# Regulator_Schematic.net
KiCad netlist of a schematic drawn in EAGLE
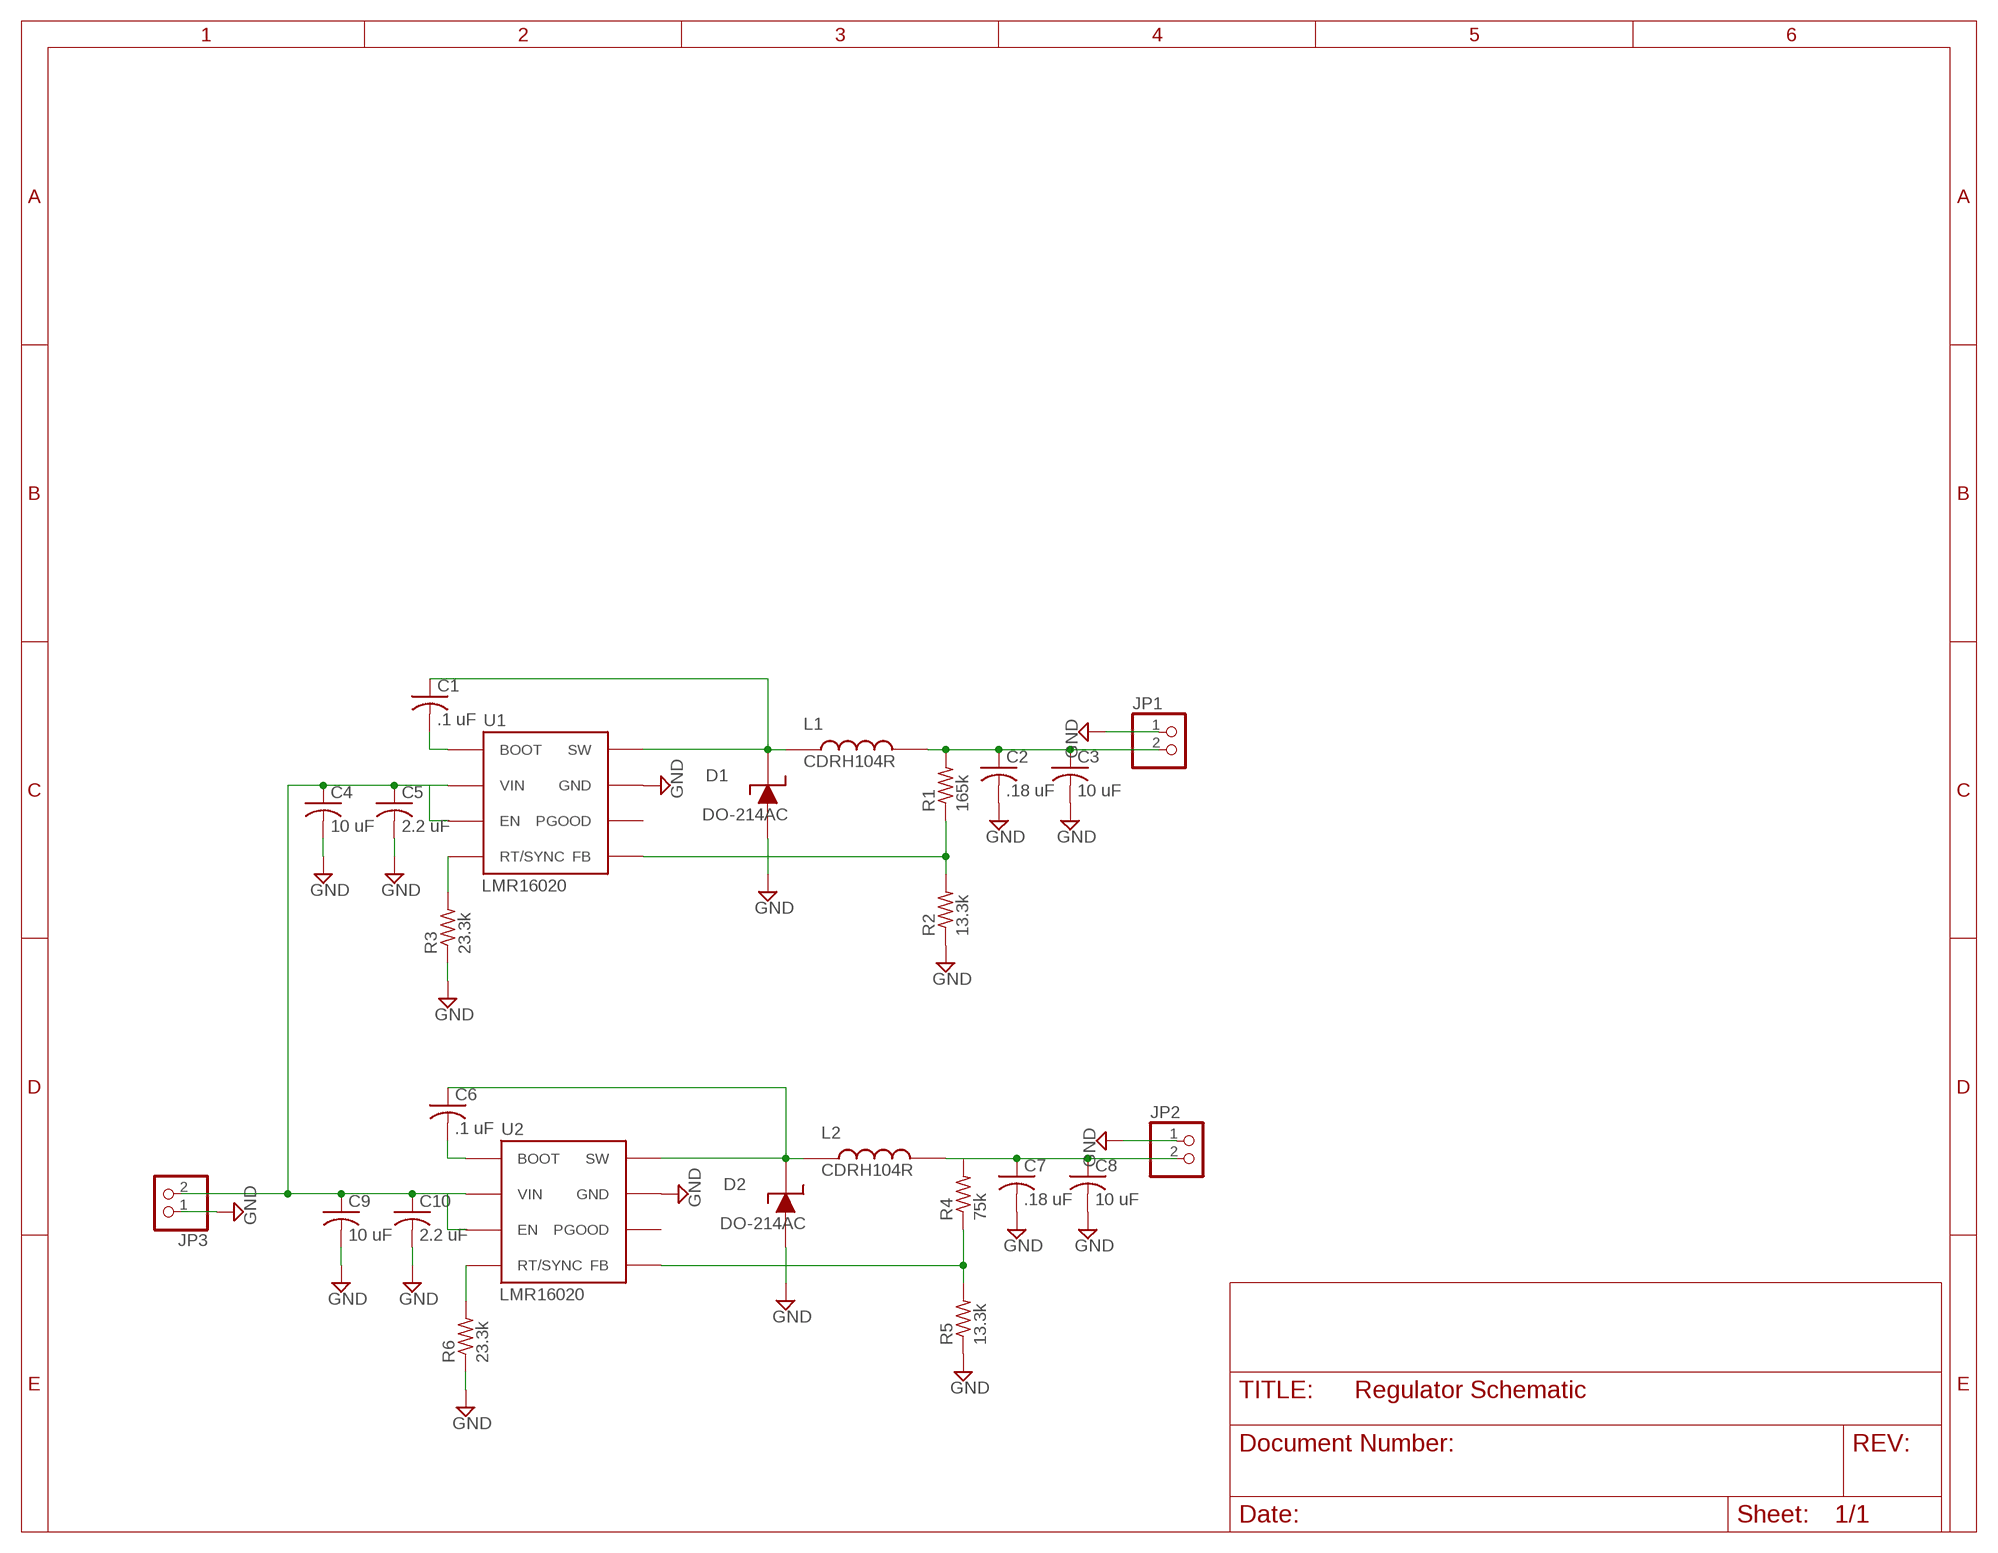
[diagram p0: schematic, sheet 1]

(export (version "E")
  (design (tool "Eeschema 10.0.6"))
  (components
    (comp (ref "C1")
      (value ".1 uF")
      (footprint "eagle-import:C0603")
      (libsource (lib "eagle-import") (part "C-USC0603"))
    )
    (comp (ref "C2")
      (value ".18 uF")
      (footprint "eagle-import:C0603")
      (libsource (lib "eagle-import") (part "C-USC0603"))
    )
    (comp (ref "C3")
      (value "10 uF")
      (footprint "eagle-import:C0603")
      (libsource (lib "eagle-import") (part "C-USC0603"))
    )
    (comp (ref "C4")
      (value "10 uF")
      (footprint "eagle-import:C1210")
      (libsource (lib "eagle-import") (part "C-USC1210"))
    )
    (comp (ref "C5")
      (value "2.2 uF")
      (footprint "eagle-import:C1210")
      (libsource (lib "eagle-import") (part "C-USC1210"))
    )
    (comp (ref "C6")
      (value ".1 uF")
      (footprint "eagle-import:C0603")
      (libsource (lib "eagle-import") (part "C-USC0603"))
    )
    (comp (ref "C7")
      (value ".18 uF")
      (footprint "eagle-import:C0603")
      (libsource (lib "eagle-import") (part "C-USC0603"))
    )
    (comp (ref "C8")
      (value "10 uF")
      (footprint "eagle-import:C0603")
      (libsource (lib "eagle-import") (part "C-USC0603"))
    )
    (comp (ref "C9")
      (value "10 uF")
      (footprint "eagle-import:C1210")
      (libsource (lib "eagle-import") (part "C-USC1210"))
    )
    (comp (ref "C10")
      (value "2.2 uF")
      (footprint "eagle-import:C1210")
      (libsource (lib "eagle-import") (part "C-USC1210"))
    )
    (comp (ref "D1")
      (value "DO-214AC")
      (footprint "eagle-import:DO-214AC")
      (libsource (lib "eagle-import") (part "DO-214AC"))
    )
    (comp (ref "D2")
      (value "DO-214AC")
      (footprint "eagle-import:DO-214AC")
      (libsource (lib "eagle-import") (part "DO-214AC"))
    )
    (comp (ref "JP1")
      (value "PINHD-1X2")
      (footprint "eagle-import:1X02")
      (libsource (lib "eagle-import") (part "PINHD-1X2"))
    )
    (comp (ref "JP2")
      (value "PINHD-1X2")
      (footprint "eagle-import:1X02")
      (libsource (lib "eagle-import") (part "PINHD-1X2"))
    )
    (comp (ref "JP3")
      (value "PINHD-1X2")
      (footprint "eagle-import:1X02")
      (libsource (lib "eagle-import") (part "PINHD-1X2"))
    )
    (comp (ref "L1")
      (value "CDRH104R")
      (footprint "eagle-import:CDRH104R")
      (libsource (lib "eagle-import") (part "CDRH104R"))
    )
    (comp (ref "L2")
      (value "CDRH104R")
      (footprint "eagle-import:CDRH104R")
      (libsource (lib "eagle-import") (part "CDRH104R"))
    )
    (comp (ref "R1")
      (value "165k")
      (footprint "eagle-import:R0603")
      (libsource (lib "eagle-import") (part "R-US_R0603"))
    )
    (comp (ref "R2")
      (value "13.3k")
      (footprint "eagle-import:R0603")
      (libsource (lib "eagle-import") (part "R-US_R0603"))
    )
    (comp (ref "R3")
      (value "23.3k")
      (footprint "eagle-import:R0603")
      (libsource (lib "eagle-import") (part "R-US_R0603"))
    )
    (comp (ref "R4")
      (value "75k")
      (footprint "eagle-import:R0603")
      (libsource (lib "eagle-import") (part "R-US_R0603"))
    )
    (comp (ref "R5")
      (value "13.3k")
      (footprint "eagle-import:R0603")
      (libsource (lib "eagle-import") (part "R-US_R0603"))
    )
    (comp (ref "R6")
      (value "23.3k")
      (footprint "eagle-import:R0603")
      (libsource (lib "eagle-import") (part "R-US_R0603"))
    )
    (comp (ref "U1")
      (value "LMR16020")
      (footprint "eagle-import:SO8")
      (libsource (lib "eagle-import") (part "LMR16020"))
    )
    (comp (ref "U2")
      (value "LMR16020")
      (footprint "eagle-import:SO8")
      (libsource (lib "eagle-import") (part "LMR16020"))
    )
  )
  (nets
    (net (code "1") (name "GND") (class "Default")
      (node (ref "C10") (pin "2") (pinfunction "2_2") (pintype "passive"))
      (node (ref "C2") (pin "2") (pinfunction "2_2") (pintype "passive"))
      (node (ref "C3") (pin "2") (pinfunction "2_2") (pintype "passive"))
      (node (ref "C4") (pin "2") (pinfunction "2_2") (pintype "passive"))
      (node (ref "C5") (pin "2") (pinfunction "2_2") (pintype "passive"))
      (node (ref "C7") (pin "2") (pinfunction "2_2") (pintype "passive"))
      (node (ref "C8") (pin "2") (pinfunction "2_2") (pintype "passive"))
      (node (ref "C9") (pin "2") (pinfunction "2_2") (pintype "passive"))
      (node (ref "D1") (pin "P$1") (pinfunction "P$1_P$1") (pintype "bidirectional"))
      (node (ref "D2") (pin "P$1") (pinfunction "P$1_P$1") (pintype "bidirectional"))
      (node (ref "JP1") (pin "1") (pinfunction "1_1") (pintype "passive"))
      (node (ref "JP2") (pin "1") (pinfunction "1_1") (pintype "passive"))
      (node (ref "JP3") (pin "1") (pinfunction "1_1") (pintype "passive"))
      (node (ref "R2") (pin "1") (pinfunction "1_1") (pintype "passive"))
      (node (ref "R3") (pin "1") (pinfunction "1_1") (pintype "passive"))
      (node (ref "R5") (pin "1") (pinfunction "1_1") (pintype "passive"))
      (node (ref "R6") (pin "1") (pinfunction "1_1") (pintype "passive"))
      (node (ref "U1") (pin "P$7") (pinfunction "GND_P$7") (pintype "bidirectional"))
      (node (ref "U1") (pin "PAD") (pinfunction "GND_PAD") (pintype "bidirectional"))
      (node (ref "U2") (pin "P$7") (pinfunction "GND_P$7") (pintype "bidirectional"))
      (node (ref "U2") (pin "PAD") (pinfunction "GND_PAD") (pintype "bidirectional"))
    )
    (net (code "2") (name "Net-(C2-Pad1)") (class "Default")
      (node (ref "C2") (pin "1") (pinfunction "1_1") (pintype "passive"))
      (node (ref "C3") (pin "1") (pinfunction "1_1") (pintype "passive"))
      (node (ref "JP1") (pin "2") (pinfunction "2_2") (pintype "passive"))
      (node (ref "L1") (pin "P$2") (pinfunction "P$2_P$2") (pintype "bidirectional"))
      (node (ref "R1") (pin "2") (pinfunction "2_2") (pintype "passive"))
    )
    (net (code "3") (name "Net-(C7-Pad1)") (class "Default")
      (node (ref "C7") (pin "1") (pinfunction "1_1") (pintype "passive"))
      (node (ref "C8") (pin "1") (pinfunction "1_1") (pintype "passive"))
      (node (ref "JP2") (pin "2") (pinfunction "2_2") (pintype "passive"))
      (node (ref "L2") (pin "P$2") (pinfunction "P$2_P$2") (pintype "bidirectional"))
      (node (ref "R4") (pin "2") (pinfunction "2_2") (pintype "passive"))
    )
    (net (code "4") (name "Net-(U1-BOOT)") (class "Default")
      (node (ref "C1") (pin "2") (pinfunction "2_2") (pintype "passive"))
      (node (ref "U1") (pin "P$1") (pinfunction "BOOT_P$1") (pintype "bidirectional"))
    )
    (net (code "5") (name "Net-(U1-EN)") (class "Default")
      (node (ref "C10") (pin "1") (pinfunction "1_1") (pintype "passive"))
      (node (ref "C4") (pin "1") (pinfunction "1_1") (pintype "passive"))
      (node (ref "C5") (pin "1") (pinfunction "1_1") (pintype "passive"))
      (node (ref "C9") (pin "1") (pinfunction "1_1") (pintype "passive"))
      (node (ref "JP3") (pin "2") (pinfunction "2_2") (pintype "passive"))
      (node (ref "U1") (pin "P$2") (pinfunction "VIN_P$2") (pintype "bidirectional"))
      (node (ref "U1") (pin "P$3") (pinfunction "EN_P$3") (pintype "bidirectional"))
      (node (ref "U2") (pin "P$2") (pinfunction "VIN_P$2") (pintype "bidirectional"))
      (node (ref "U2") (pin "P$3") (pinfunction "EN_P$3") (pintype "bidirectional"))
    )
    (net (code "6") (name "Net-(U1-FB)") (class "Default")
      (node (ref "R1") (pin "1") (pinfunction "1_1") (pintype "passive"))
      (node (ref "R2") (pin "2") (pinfunction "2_2") (pintype "passive"))
      (node (ref "U1") (pin "P$5") (pinfunction "FB_P$5") (pintype "bidirectional"))
    )
    (net (code "7") (name "Net-(U1-RT{slash}SYNC)") (class "Default")
      (node (ref "R3") (pin "2") (pinfunction "2_2") (pintype "passive"))
      (node (ref "U1") (pin "P$4") (pinfunction "RT/SYNC_P$4") (pintype "bidirectional"))
    )
    (net (code "8") (name "Net-(U1-SW)") (class "Default")
      (node (ref "C1") (pin "1") (pinfunction "1_1") (pintype "passive"))
      (node (ref "D1") (pin "P$2") (pinfunction "P$2_P$2") (pintype "bidirectional"))
      (node (ref "L1") (pin "P$1") (pinfunction "P$1_P$1") (pintype "bidirectional"))
      (node (ref "U1") (pin "P$8") (pinfunction "SW_P$8") (pintype "bidirectional"))
    )
    (net (code "9") (name "Net-(U2-BOOT)") (class "Default")
      (node (ref "C6") (pin "2") (pinfunction "2_2") (pintype "passive"))
      (node (ref "U2") (pin "P$1") (pinfunction "BOOT_P$1") (pintype "bidirectional"))
    )
    (net (code "10") (name "Net-(U2-FB)") (class "Default")
      (node (ref "R4") (pin "1") (pinfunction "1_1") (pintype "passive"))
      (node (ref "R5") (pin "2") (pinfunction "2_2") (pintype "passive"))
      (node (ref "U2") (pin "P$5") (pinfunction "FB_P$5") (pintype "bidirectional"))
    )
    (net (code "11") (name "Net-(U2-RT{slash}SYNC)") (class "Default")
      (node (ref "R6") (pin "2") (pinfunction "2_2") (pintype "passive"))
      (node (ref "U2") (pin "P$4") (pinfunction "RT/SYNC_P$4") (pintype "bidirectional"))
    )
    (net (code "12") (name "Net-(U2-SW)") (class "Default")
      (node (ref "C6") (pin "1") (pinfunction "1_1") (pintype "passive"))
      (node (ref "D2") (pin "P$2") (pinfunction "P$2_P$2") (pintype "bidirectional"))
      (node (ref "L2") (pin "P$1") (pinfunction "P$1_P$1") (pintype "bidirectional"))
      (node (ref "U2") (pin "P$8") (pinfunction "SW_P$8") (pintype "bidirectional"))
    )
    (net (code "13") (name "unconnected-(U1-PGOOD-PadP$6)") (class "Default")
      (node (ref "U1") (pin "P$6") (pinfunction "PGOOD_P$6") (pintype "bidirectional"))
    )
    (net (code "14") (name "unconnected-(U2-PGOOD-PadP$6)") (class "Default")
      (node (ref "U2") (pin "P$6") (pinfunction "PGOOD_P$6") (pintype "bidirectional"))
    )
  )
)
